# LoPoSwitch-BLE.net
KiCad netlist of a schematic drawn in EAGLE
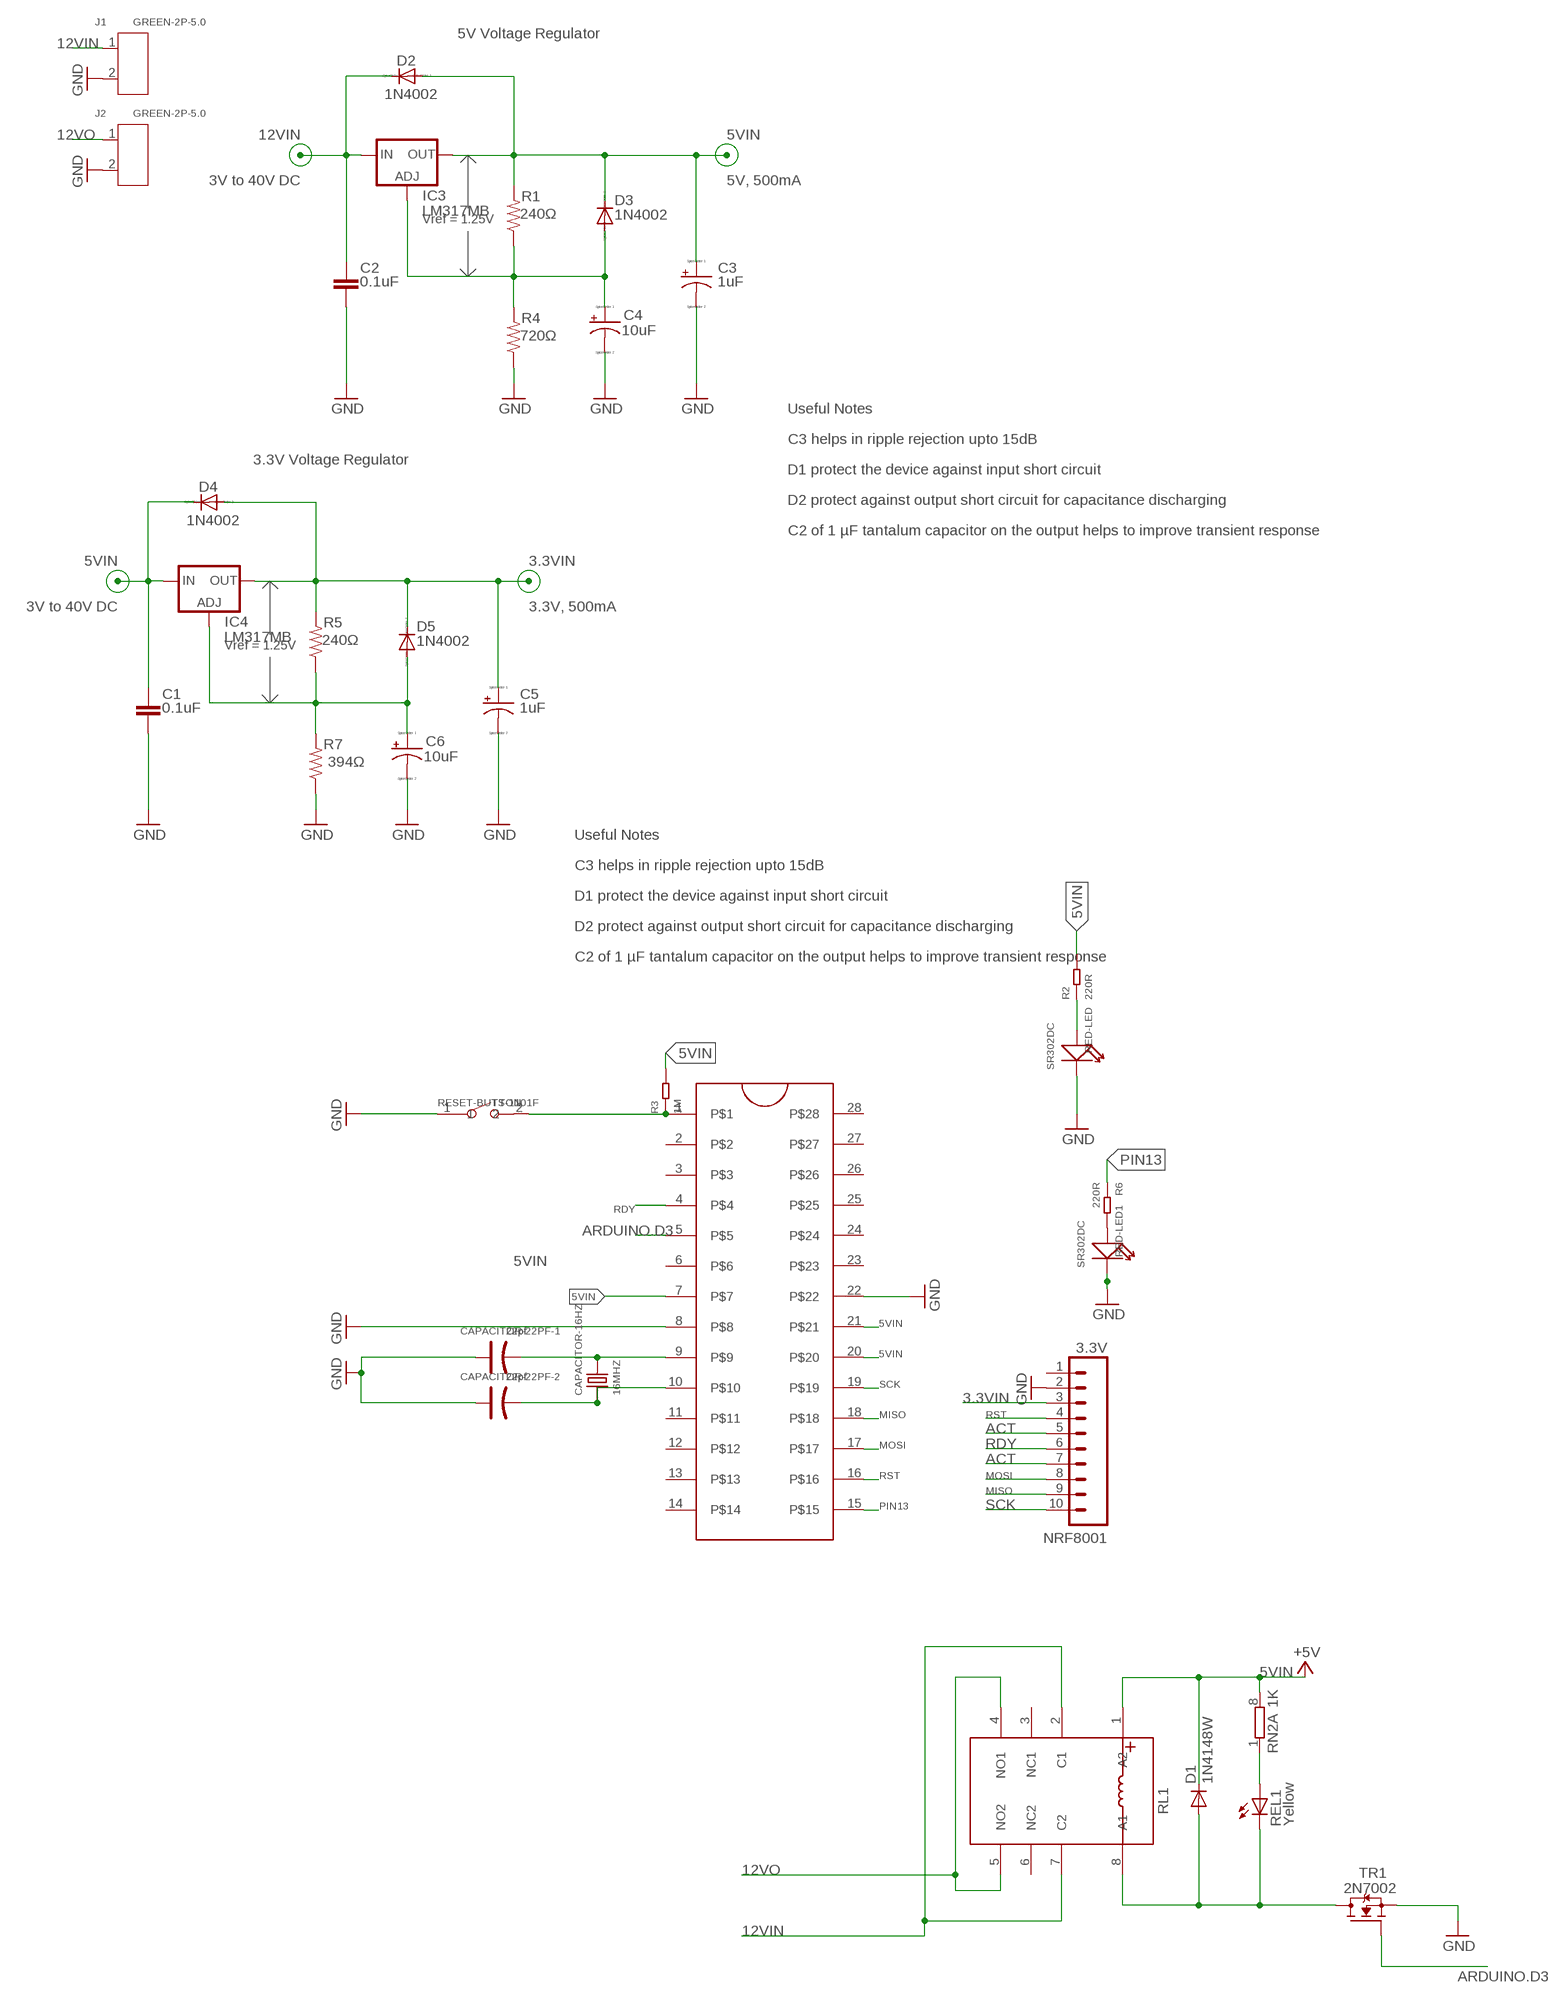
[diagram p0: schematic, sheet 1]

(export (version "E")
  (design (tool "Eeschema 10.0.6"))
  (components
    (comp (ref "ATMEGA328")
      (value "ZIFSOCKET-28-3ZIFFSOCKET-28-3")
      (footprint "eagle-import:DIL28-3-ZIF_SOCKET")
      (libsource (lib "eagle-import") (part "ZIFSOCKET-28-3ZIFFSOCKET-28-3"))
    )
    (comp (ref "C1")
      (value "0.1uF")
      (footprint "eagle-import:C075-052X106")
      (libsource (lib "eagle-import") (part "C-EU075-052X106"))
    )
    (comp (ref "C2")
      (value "0.1uF")
      (footprint "eagle-import:C075-052X106")
      (libsource (lib "eagle-import") (part "C-EU075-052X106"))
    )
    (comp (ref "C3")
      (value "1uF")
      (footprint "eagle-import:085CS_1AR")
      (libsource (lib "eagle-import") (part "CPOL-US085CS-1AR"))
    )
    (comp (ref "C4")
      (value "10uF")
      (footprint "eagle-import:085CS_1AR")
      (libsource (lib "eagle-import") (part "CPOL-US085CS-1AR"))
    )
    (comp (ref "C5")
      (value "1uF")
      (footprint "eagle-import:085CS_1AR")
      (libsource (lib "eagle-import") (part "CPOL-US085CS-1AR"))
    )
    (comp (ref "C6")
      (value "10uF")
      (footprint "eagle-import:085CS_1AR")
      (libsource (lib "eagle-import") (part "CPOL-US085CS-1AR"))
    )
    (comp (ref "CAPACITOR-16HZ")
      (value "16MHZ")
      (footprint "eagle-import:HC49US")
      (fields (field (name "MPN") "49S/18PF"))
      (libsource (lib "eagle-import") (part "DIP-CRYSTAL-16MHZ-18PF-30PPM-50R(HC49US)"))
    )
    (comp (ref "CAPACITOR-22PF-1")
      (value "22pf")
      (footprint "eagle-import:PC-D5.3MM")
      (fields (field (name "MPN") "KS 100uF/16V"))
      (libsource (lib "eagle-import") (part "DIP-ALUMINUM-47UF-16V(D5-H7MM)"))
    )
    (comp (ref "CAPACITOR-22PF-2")
      (value "22pf")
      (footprint "eagle-import:PC-D5.3MM")
      (fields (field (name "MPN") "KS 100uF/16V"))
      (libsource (lib "eagle-import") (part "DIP-ALUMINUM-47UF-16V(D5-H7MM)"))
    )
    (comp (ref "D1")
      (value "1N4148W")
      (footprint "eagle-import:SOD123")
      (libsource (lib "eagle-import") (part "0290_1N4148W"))
    )
    (comp (ref "D2")
      (value "1N4002")
      (footprint "eagle-import:DO41-10")
      (libsource (lib "eagle-import") (part "1N4004"))
    )
    (comp (ref "D3")
      (value "1N4002")
      (footprint "eagle-import:DO41-10")
      (libsource (lib "eagle-import") (part "1N4004"))
    )
    (comp (ref "D4")
      (value "1N4002")
      (footprint "eagle-import:DO41-10")
      (libsource (lib "eagle-import") (part "1N4004"))
    )
    (comp (ref "D5")
      (value "1N4002")
      (footprint "eagle-import:DO41-10")
      (libsource (lib "eagle-import") (part "1N4004"))
    )
    (comp (ref "IC3")
      (value "LM317MB")
      (footprint "eagle-import:TO220L1")
      (fields (field (name "MPN") "LM317MABTG"))
      (libsource (lib "eagle-import") (part "LM317?MB"))
    )
    (comp (ref "IC4")
      (value "LM317MB")
      (footprint "eagle-import:TO220L1")
      (fields (field (name "MPN") "LM317MABTG"))
      (libsource (lib "eagle-import") (part "LM317?MB"))
    )
    (comp (ref "J1")
      (value "GREEN-2P-5.0")
      (footprint "eagle-import:H2-5.0-10.5X8.0MM")
      (libsource (lib "eagle-import") (part "SCREW-TERMINAL-GREEN(2P-5.0)"))
    )
    (comp (ref "J2")
      (value "GREEN-2P-5.0")
      (footprint "eagle-import:H2-5.0-10.5X8.0MM")
      (libsource (lib "eagle-import") (part "SCREW-TERMINAL-GREEN(2P-5.0)"))
    )
    (comp (ref "NRF8001")
      (value "3.3V")
      (footprint "eagle-import:1X10")
      (libsource (lib "eagle-import") (part "M10SILK_FEMALE_PTH"))
    )
    (comp (ref "R1")
      (value "240Ω")
      (footprint "eagle-import:M0805")
      (libsource (lib "eagle-import") (part "R-US_M0805"))
    )
    (comp (ref "R2")
      (value "220R")
      (footprint "eagle-import:PR-D2.3XL6.5MM")
      (fields (field (name "MPN") "FHCFR-1/4W-221J"))
      (libsource (lib "eagle-import") (part "DIP-RES-220R-5%-1/4W(PR-D2.3XL6.5MM)"))
    )
    (comp (ref "R3")
      (value "1M")
      (footprint "eagle-import:PR-D2.3XL6.5MM")
      (fields (field (name "MPN") "FHCFR-1/4W-105J"))
      (libsource (lib "eagle-import") (part "DIP-RES-1M-5%-1/4W(PR-D2.3XL6.5MM)"))
    )
    (comp (ref "R4")
      (value "720Ω")
      (footprint "eagle-import:M0805")
      (libsource (lib "eagle-import") (part "R-US_M0805"))
    )
    (comp (ref "R5")
      (value "240Ω")
      (footprint "eagle-import:M0805")
      (libsource (lib "eagle-import") (part "R-US_M0805"))
    )
    (comp (ref "R6")
      (value "220R")
      (footprint "eagle-import:PR-D2.3XL6.5MM")
      (fields (field (name "MPN") "FHCFR-1/4W-221J"))
      (libsource (lib "eagle-import") (part "DIP-RES-220R-5%-1/4W(PR-D2.3XL6.5MM)"))
    )
    (comp (ref "R7")
      (value "394Ω")
      (footprint "eagle-import:M0805")
      (libsource (lib "eagle-import") (part "R-US_M0805"))
    )
    (comp (ref "RED-LED")
      (value "SR302DC")
      (footprint "eagle-import:LED2-2.54-D3.0MM")
      (libsource (lib "eagle-import") (part "DIP-LED-RED-RED(2P-D3MM)"))
    )
    (comp (ref "RED-LED1")
      (value "SR302DC")
      (footprint "eagle-import:LED2-2.54-D3.0MM")
      (libsource (lib "eagle-import") (part "DIP-LED-RED-RED(2P-D3MM)"))
    )
    (comp (ref "REL1")
      (value "Yellow")
      (footprint "eagle-import:CHIPLED_0805")
      (fields (field (name "PART_NUMBER") "KPT-2012YC"))
      (libsource (lib "eagle-import") (part "0044_KPT-2012YC"))
    )
    (comp (ref "RESET-BUTTON")
      (value "TS-1101F")
      (footprint "eagle-import:SW2-5.0-6.0X3.0X4.3MM")
      (libsource (lib "eagle-import") (part "DIP-BUTTON(2P-6.0X3.0X4.3MM)-TS-1101F"))
    )
    (comp (ref "RL1")
      (value "1045_G5V-2-H1")
      (footprint "eagle-import:RELE'-30SSERIES-DIL-2X")
      (fields (field (name "PART_NUMBER") "G5V-2-H1"))
      (libsource (lib "eagle-import") (part "1045_G5V-2-H1"))
    )
    (comp (ref "RN2")
      (value "1K")
      (footprint "eagle-import:CAY16")
      (fields (field (name "PART_NUMBER") "064R_1K_/_CAY16-102J4LF"))
      (libsource (lib "eagle-import") (part "0005_064R_1K_/_CAY16-102J4LF"))
    )
    (comp (ref "TR1")
      (value "2N7002")
      (footprint "eagle-import:SOT-23")
      (libsource (lib "eagle-import") (part "1612_2N7002LT1G"))
    )
  )
  (nets
    (net (code "1") (name "/3.3VIN") (class "Default")
      (node (ref "C5") (pin "+") (pinfunction "+_+") (pintype "passive"))
      (node (ref "D4") (pin "A") (pinfunction "A_A") (pintype "passive"))
      (node (ref "D5") (pin "C") (pinfunction "C_C") (pintype "passive"))
      (node (ref "IC4") (pin "2") (pinfunction "OUT_2") (pintype "passive"))
      (node (ref "NRF8001") (pin "3") (pinfunction "3_3") (pintype "passive"))
      (node (ref "R5") (pin "2") (pinfunction "2_2") (pintype "passive"))
    )
    (net (code "2") (name "/12VIN") (class "Default")
      (node (ref "C2") (pin "1") (pinfunction "1_1") (pintype "passive"))
      (node (ref "D2") (pin "C") (pinfunction "C_C") (pintype "passive"))
      (node (ref "IC3") (pin "3") (pinfunction "IN_3") (pintype "input"))
      (node (ref "J1") (pin "1") (pinfunction "1_1") (pintype "bidirectional"))
      (node (ref "RL1") (pin "2") (pinfunction "C1_2") (pintype "bidirectional"))
      (node (ref "RL1") (pin "7") (pinfunction "C2_7") (pintype "bidirectional"))
    )
    (net (code "3") (name "/12VO") (class "Default")
      (node (ref "J2") (pin "1") (pinfunction "1_1") (pintype "bidirectional"))
      (node (ref "RL1") (pin "4") (pinfunction "NO1_4") (pintype "bidirectional"))
      (node (ref "RL1") (pin "5") (pinfunction "NO2_5") (pintype "bidirectional"))
    )
    (net (code "4") (name "/ACT") (class "Default")
      (node (ref "NRF8001") (pin "5") (pinfunction "5_5") (pintype "passive"))
      (node (ref "NRF8001") (pin "7") (pinfunction "7_7") (pintype "passive"))
    )
    (net (code "5") (name "/ARDUINO.D3") (class "Default")
      (node (ref "ATMEGA328") (pin "5") (pinfunction "P$5_5") (pintype "bidirectional"))
      (node (ref "TR1") (pin "3") (pinfunction "G_3") (pintype "passive"))
    )
    (net (code "6") (name "/MISO") (class "Default")
      (node (ref "ATMEGA328") (pin "18") (pinfunction "P$18_18") (pintype "bidirectional"))
      (node (ref "NRF8001") (pin "9") (pinfunction "9_9") (pintype "passive"))
    )
    (net (code "7") (name "/MOSI") (class "Default")
      (node (ref "ATMEGA328") (pin "17") (pinfunction "P$17_17") (pintype "bidirectional"))
      (node (ref "NRF8001") (pin "8") (pinfunction "8_8") (pintype "passive"))
    )
    (net (code "8") (name "/RDY") (class "Default")
      (node (ref "ATMEGA328") (pin "4") (pinfunction "P$4_4") (pintype "bidirectional"))
      (node (ref "NRF8001") (pin "6") (pinfunction "6_6") (pintype "passive"))
    )
    (net (code "9") (name "/RST") (class "Default")
      (node (ref "ATMEGA328") (pin "16") (pinfunction "P$16_16") (pintype "bidirectional"))
      (node (ref "NRF8001") (pin "4") (pinfunction "4_4") (pintype "passive"))
    )
    (net (code "10") (name "/SCK") (class "Default")
      (node (ref "ATMEGA328") (pin "19") (pinfunction "P$19_19") (pintype "bidirectional"))
      (node (ref "NRF8001") (pin "10") (pinfunction "10_10") (pintype "passive"))
    )
    (net (code "11") (name "5VIN") (class "Default")
      (node (ref "ATMEGA328") (pin "20") (pinfunction "P$20_20") (pintype "bidirectional"))
      (node (ref "ATMEGA328") (pin "21") (pinfunction "P$21_21") (pintype "bidirectional"))
      (node (ref "ATMEGA328") (pin "7") (pinfunction "P$7_7") (pintype "bidirectional"))
      (node (ref "C1") (pin "1") (pinfunction "1_1") (pintype "passive"))
      (node (ref "C3") (pin "+") (pinfunction "+_+") (pintype "passive"))
      (node (ref "D1") (pin "C") (pinfunction "C_C") (pintype "passive"))
      (node (ref "D2") (pin "A") (pinfunction "A_A") (pintype "passive"))
      (node (ref "D3") (pin "C") (pinfunction "C_C") (pintype "passive"))
      (node (ref "D4") (pin "C") (pinfunction "C_C") (pintype "passive"))
      (node (ref "IC3") (pin "2") (pinfunction "OUT_2") (pintype "passive"))
      (node (ref "IC4") (pin "3") (pinfunction "IN_3") (pintype "input"))
      (node (ref "R1") (pin "2") (pinfunction "2_2") (pintype "passive"))
      (node (ref "R2") (pin "2") (pinfunction "2_2") (pintype "passive"))
      (node (ref "R3") (pin "2") (pinfunction "2_2") (pintype "passive"))
      (node (ref "RL1") (pin "1") (pinfunction "A2_1") (pintype "bidirectional"))
      (node (ref "RN2") (pin "8") (pinfunction "2_8") (pintype "passive"))
    )
    (net (code "12") (name "GND") (class "Default")
      (node (ref "ATMEGA328") (pin "22") (pinfunction "P$22_22") (pintype "bidirectional"))
      (node (ref "ATMEGA328") (pin "8") (pinfunction "P$8_8") (pintype "bidirectional"))
      (node (ref "C1") (pin "2") (pinfunction "2_2") (pintype "passive"))
      (node (ref "C2") (pin "2") (pinfunction "2_2") (pintype "passive"))
      (node (ref "C3") (pin "-") (pinfunction "-_-") (pintype "passive"))
      (node (ref "C4") (pin "-") (pinfunction "-_-") (pintype "passive"))
      (node (ref "C5") (pin "-") (pinfunction "-_-") (pintype "passive"))
      (node (ref "C6") (pin "-") (pinfunction "-_-") (pintype "passive"))
      (node (ref "CAPACITOR-22PF-1") (pin "+") (pinfunction "+_+") (pintype "passive"))
      (node (ref "CAPACITOR-22PF-2") (pin "+") (pinfunction "+_+") (pintype "passive"))
      (node (ref "J1") (pin "2") (pinfunction "2_2") (pintype "bidirectional"))
      (node (ref "J2") (pin "2") (pinfunction "2_2") (pintype "bidirectional"))
      (node (ref "NRF8001") (pin "2") (pinfunction "2_2") (pintype "passive"))
      (node (ref "R4") (pin "1") (pinfunction "1_1") (pintype "passive"))
      (node (ref "R7") (pin "1") (pinfunction "1_1") (pintype "passive"))
      (node (ref "RED-LED") (pin "K") (pinfunction "-_K") (pintype "passive"))
      (node (ref "RED-LED1") (pin "K") (pinfunction "-_K") (pintype "passive"))
      (node (ref "RESET-BUTTON") (pin "1") (pinfunction "1_1") (pintype "bidirectional"))
      (node (ref "TR1") (pin "2") (pinfunction "S_2") (pintype "passive"))
    )
    (net (code "13") (name "Net-(ATMEGA328-P$1)") (class "Default")
      (node (ref "ATMEGA328") (pin "1") (pinfunction "P$1_1") (pintype "bidirectional"))
      (node (ref "R3") (pin "1") (pinfunction "1_1") (pintype "passive"))
      (node (ref "RESET-BUTTON") (pin "2") (pinfunction "2_2") (pintype "bidirectional"))
    )
    (net (code "14") (name "Net-(ATMEGA328-P$9)") (class "Default")
      (node (ref "ATMEGA328") (pin "9") (pinfunction "P$9_9") (pintype "bidirectional"))
      (node (ref "CAPACITOR-16HZ") (pin "2") (pinfunction "2_2") (pintype "passive"))
      (node (ref "CAPACITOR-22PF-1") (pin "-") (pinfunction "-_-") (pintype "passive"))
    )
    (net (code "15") (name "Net-(ATMEGA328-P$10)") (class "Default")
      (node (ref "ATMEGA328") (pin "10") (pinfunction "P$10_10") (pintype "bidirectional"))
      (node (ref "CAPACITOR-16HZ") (pin "1") (pinfunction "1_1") (pintype "passive"))
      (node (ref "CAPACITOR-22PF-2") (pin "-") (pinfunction "-_-") (pintype "passive"))
    )
    (net (code "16") (name "Net-(IC3-ADJ)") (class "Default")
      (node (ref "C4") (pin "+") (pinfunction "+_+") (pintype "passive"))
      (node (ref "D3") (pin "A") (pinfunction "A_A") (pintype "passive"))
      (node (ref "IC3") (pin "1") (pinfunction "ADJ_1") (pintype "input"))
      (node (ref "R1") (pin "1") (pinfunction "1_1") (pintype "passive"))
      (node (ref "R4") (pin "2") (pinfunction "2_2") (pintype "passive"))
    )
    (net (code "17") (name "Net-(IC4-ADJ)") (class "Default")
      (node (ref "C6") (pin "+") (pinfunction "+_+") (pintype "passive"))
      (node (ref "D5") (pin "A") (pinfunction "A_A") (pintype "passive"))
      (node (ref "IC4") (pin "1") (pinfunction "ADJ_1") (pintype "input"))
      (node (ref "R5") (pin "1") (pinfunction "1_1") (pintype "passive"))
      (node (ref "R7") (pin "2") (pinfunction "2_2") (pintype "passive"))
    )
    (net (code "18") (name "Net-(RED-LED-+)") (class "Default")
      (node (ref "R2") (pin "1") (pinfunction "1_1") (pintype "passive"))
      (node (ref "RED-LED") (pin "A") (pinfunction "+_A") (pintype "passive"))
    )
    (net (code "19") (name "Net-(RED-LED1-+)") (class "Default")
      (node (ref "R6") (pin "2") (pinfunction "2_2") (pintype "passive"))
      (node (ref "RED-LED1") (pin "A") (pinfunction "+_A") (pintype "passive"))
    )
    (net (code "20") (name "Net-(REL1-PadA)") (class "Default")
      (node (ref "REL1") (pin "A") (pinfunction "A_A") (pintype "passive"))
      (node (ref "RN2") (pin "1") (pinfunction "1_1") (pintype "passive"))
    )
    (net (code "21") (name "Net-(RL1-A1)") (class "Default")
      (node (ref "D1") (pin "A") (pinfunction "A_A") (pintype "passive"))
      (node (ref "REL1") (pin "C") (pinfunction "C_C") (pintype "passive"))
      (node (ref "RL1") (pin "8") (pinfunction "A1_8") (pintype "bidirectional"))
      (node (ref "TR1") (pin "1") (pinfunction "D_1") (pintype "passive"))
    )
    (net (code "22") (name "PIN13") (class "Default")
      (node (ref "ATMEGA328") (pin "15") (pinfunction "P$15_15") (pintype "bidirectional"))
      (node (ref "R6") (pin "1") (pinfunction "1_1") (pintype "passive"))
    )
    (net (code "23") (name "unconnected-(ATMEGA328-P$2-Pad2)") (class "Default")
      (node (ref "ATMEGA328") (pin "2") (pinfunction "P$2_2") (pintype "bidirectional"))
    )
    (net (code "24") (name "unconnected-(ATMEGA328-P$3-Pad3)") (class "Default")
      (node (ref "ATMEGA328") (pin "3") (pinfunction "P$3_3") (pintype "bidirectional"))
    )
    (net (code "25") (name "unconnected-(ATMEGA328-P$6-Pad6)") (class "Default")
      (node (ref "ATMEGA328") (pin "6") (pinfunction "P$6_6") (pintype "bidirectional"))
    )
    (net (code "26") (name "unconnected-(ATMEGA328-P$11-Pad11)") (class "Default")
      (node (ref "ATMEGA328") (pin "11") (pinfunction "P$11_11") (pintype "bidirectional"))
    )
    (net (code "27") (name "unconnected-(ATMEGA328-P$12-Pad12)") (class "Default")
      (node (ref "ATMEGA328") (pin "12") (pinfunction "P$12_12") (pintype "bidirectional"))
    )
    (net (code "28") (name "unconnected-(ATMEGA328-P$13-Pad13)") (class "Default")
      (node (ref "ATMEGA328") (pin "13") (pinfunction "P$13_13") (pintype "bidirectional"))
    )
    (net (code "29") (name "unconnected-(ATMEGA328-P$14-Pad14)") (class "Default")
      (node (ref "ATMEGA328") (pin "14") (pinfunction "P$14_14") (pintype "bidirectional"))
    )
    (net (code "30") (name "unconnected-(ATMEGA328-P$23-Pad23)") (class "Default")
      (node (ref "ATMEGA328") (pin "23") (pinfunction "P$23_23") (pintype "bidirectional"))
    )
    (net (code "31") (name "unconnected-(ATMEGA328-P$24-Pad24)") (class "Default")
      (node (ref "ATMEGA328") (pin "24") (pinfunction "P$24_24") (pintype "bidirectional"))
    )
    (net (code "32") (name "unconnected-(ATMEGA328-P$25-Pad25)") (class "Default")
      (node (ref "ATMEGA328") (pin "25") (pinfunction "P$25_25") (pintype "bidirectional"))
    )
    (net (code "33") (name "unconnected-(ATMEGA328-P$26-Pad26)") (class "Default")
      (node (ref "ATMEGA328") (pin "26") (pinfunction "P$26_26") (pintype "bidirectional"))
    )
    (net (code "34") (name "unconnected-(ATMEGA328-P$27-Pad27)") (class "Default")
      (node (ref "ATMEGA328") (pin "27") (pinfunction "P$27_27") (pintype "bidirectional"))
    )
    (net (code "35") (name "unconnected-(ATMEGA328-P$28-Pad28)") (class "Default")
      (node (ref "ATMEGA328") (pin "28") (pinfunction "P$28_28") (pintype "bidirectional"))
    )
    (net (code "36") (name "unconnected-(NRF8001-Pad1)") (class "Default")
      (node (ref "NRF8001") (pin "1") (pinfunction "1_1") (pintype "passive"))
    )
    (net (code "37") (name "unconnected-(RL1-NC1-Pad3)") (class "Default")
      (node (ref "RL1") (pin "3") (pinfunction "NC1_3") (pintype "bidirectional"))
    )
    (net (code "38") (name "unconnected-(RL1-NC2-Pad6)") (class "Default")
      (node (ref "RL1") (pin "6") (pinfunction "NC2_6") (pintype "bidirectional"))
    )
  )
)
